# mcuCore.net
KiCad netlist of a schematic drawn in Altium Designer
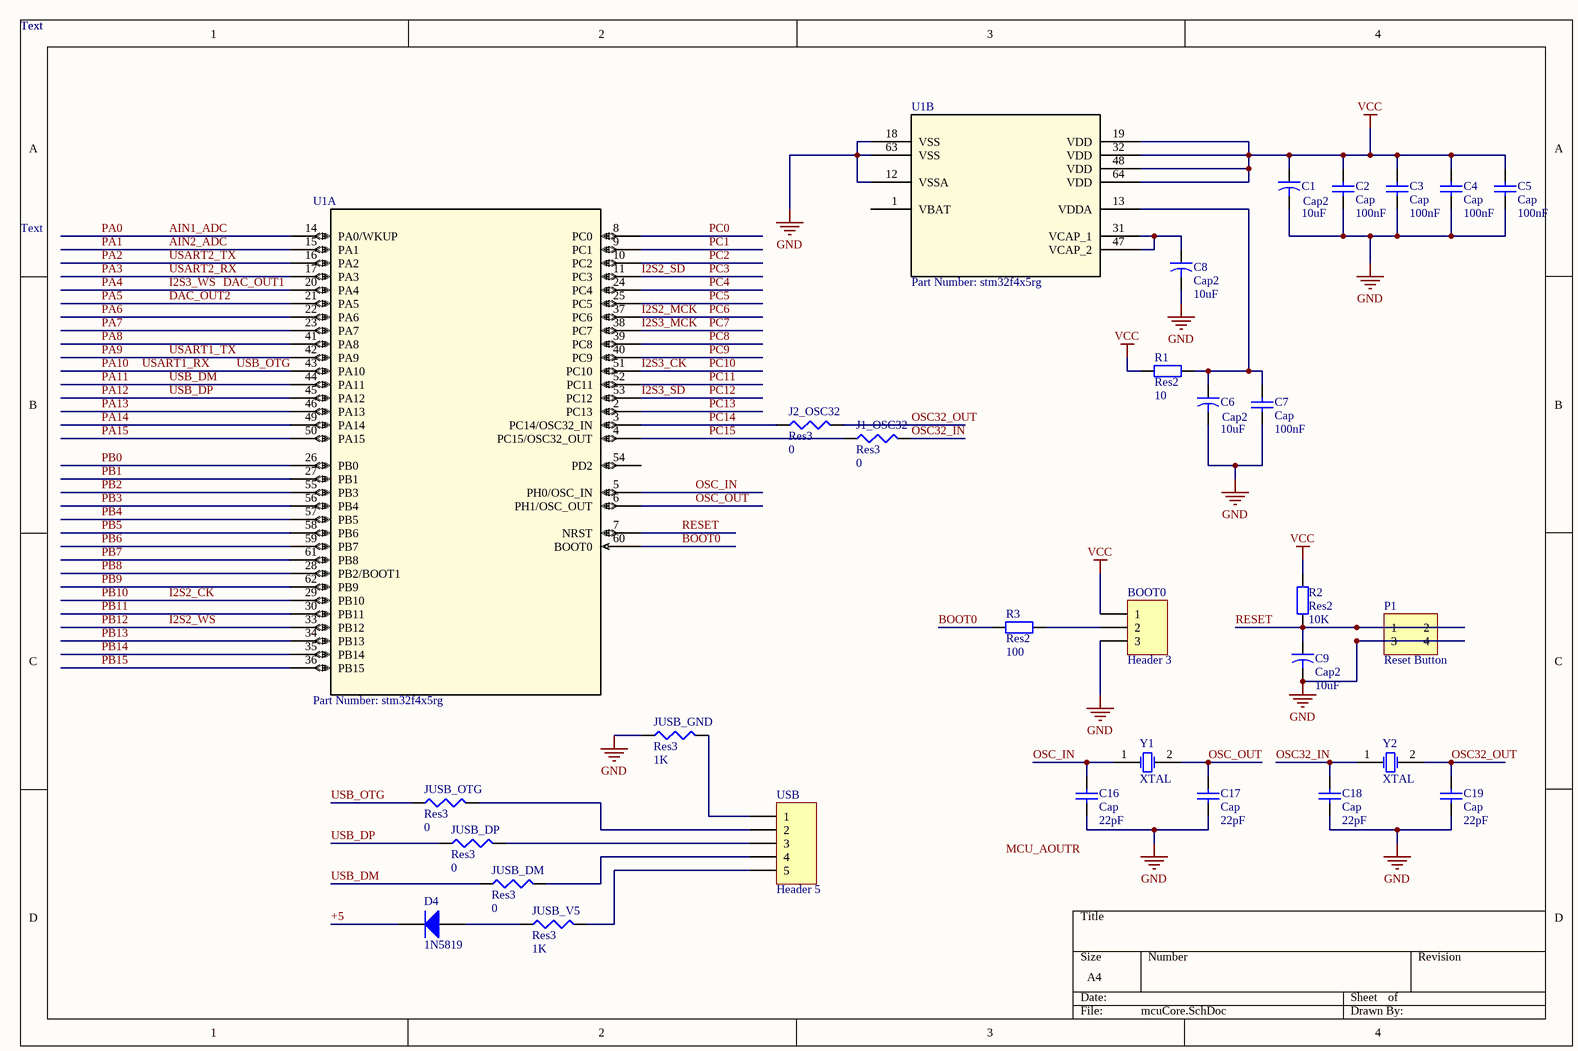
[diagram p0: mcuCore.SchDoc]

(export (version "E")
  (design (tool "Eeschema 10.0.6"))
  (components
    (comp (ref "BOOT0")
      (value "Header 3")
      (footprint "HDR1X3")
      (description "Header, 3-Pin")
      (fields (field (name "PUBLISHER") "Altium Limited"))
      (libsource (lib "Miscellaneous Connectors") (part "Header 3"))
    )
    (comp (ref "C1")
      (value "Cap2")
      (footprint "Cap5x10")
      (description "Capacitor")
      (fields (field (name "ALTIUM_VALUE") "10uF") (field (name "PUBLISHER") "Altium Limited"))
      (libsource (lib "Miscellaneous Devices") (part "Cap2"))
    )
    (comp (ref "C2")
      (value "Cap")
      (footprint "1608[0603]")
      (description "Capacitor")
      (fields (field (name "ALTIUM_VALUE") "100nF") (field (name "PUBLISHER") "Altium Limited"))
      (libsource (lib "Miscellaneous Devices") (part "Cap"))
    )
    (comp (ref "C3")
      (value "Cap")
      (footprint "1608[0603]")
      (description "Capacitor")
      (fields (field (name "ALTIUM_VALUE") "100nF") (field (name "PUBLISHER") "Altium Limited"))
      (libsource (lib "Miscellaneous Devices") (part "Cap"))
    )
    (comp (ref "C4")
      (value "Cap")
      (footprint "1608[0603]")
      (description "Capacitor")
      (fields (field (name "ALTIUM_VALUE") "100nF") (field (name "PUBLISHER") "Altium Limited"))
      (libsource (lib "Miscellaneous Devices") (part "Cap"))
    )
    (comp (ref "C5")
      (value "Cap")
      (footprint "1608[0603]")
      (description "Capacitor")
      (fields (field (name "ALTIUM_VALUE") "100nF") (field (name "PUBLISHER") "Altium Limited"))
      (libsource (lib "Miscellaneous Devices") (part "Cap"))
    )
    (comp (ref "C6")
      (value "Cap2")
      (footprint "Cap5x10")
      (description "Capacitor")
      (fields (field (name "ALTIUM_VALUE") "10uF") (field (name "PUBLISHER") "Altium Limited"))
      (libsource (lib "Miscellaneous Devices") (part "Cap2"))
    )
    (comp (ref "C7")
      (value "Cap")
      (footprint "1608[0603]")
      (description "Capacitor")
      (fields (field (name "ALTIUM_VALUE") "100nF") (field (name "PUBLISHER") "Altium Limited"))
      (libsource (lib "Miscellaneous Devices") (part "Cap"))
    )
    (comp (ref "C8")
      (value "Cap2")
      (footprint "Cap5x10")
      (description "Capacitor")
      (fields (field (name "ALTIUM_VALUE") "10uF") (field (name "PUBLISHER") "Altium Limited"))
      (libsource (lib "Miscellaneous Devices") (part "Cap2"))
    )
    (comp (ref "C9")
      (value "Cap2")
      (footprint "Cap5x10")
      (description "Capacitor")
      (fields (field (name "ALTIUM_VALUE") "10uF") (field (name "PUBLISHER") "Altium Limited"))
      (libsource (lib "Miscellaneous Devices") (part "Cap2"))
    )
    (comp (ref "C16")
      (value "Cap")
      (footprint "1608[0603]")
      (description "Capacitor")
      (fields (field (name "ALTIUM_VALUE") "22pF") (field (name "PUBLISHER") "Altium Limited"))
      (libsource (lib "Miscellaneous Devices") (part "Cap"))
    )
    (comp (ref "C17")
      (value "Cap")
      (footprint "1608[0603]")
      (description "Capacitor")
      (fields (field (name "ALTIUM_VALUE") "22pF") (field (name "PUBLISHER") "Altium Limited"))
      (libsource (lib "Miscellaneous Devices") (part "Cap"))
    )
    (comp (ref "C18")
      (value "Cap")
      (footprint "1608[0603]")
      (description "Capacitor")
      (fields (field (name "ALTIUM_VALUE") "22pF") (field (name "PUBLISHER") "Altium Limited"))
      (libsource (lib "Miscellaneous Devices") (part "Cap"))
    )
    (comp (ref "C19")
      (value "Cap")
      (footprint "1608[0603]")
      (description "Capacitor")
      (fields (field (name "ALTIUM_VALUE") "22pF") (field (name "PUBLISHER") "Altium Limited"))
      (libsource (lib "Miscellaneous Devices") (part "Cap"))
    )
    (comp (ref "D4")
      (value "1N5819")
      (footprint "425")
      (description "High Conductance Fast Diode")
      (fields (field (name "PUBLISHER") "Altium Limited"))
      (libsource (lib "Miscellaneous Devices") (part "Diode 1N4148"))
    )
    (comp (ref "J1_OSC32")
      (value "Res3")
      (footprint "JUMPER2")
      (description "Resistor")
      (fields (field (name "ALTIUM_VALUE") "0") (field (name "PUBLISHER") "Altium Limited"))
      (libsource (lib "Miscellaneous Devices") (part "Res3"))
    )
    (comp (ref "J2_OSC32")
      (value "Res3")
      (footprint "JUMPER2")
      (description "Resistor")
      (fields (field (name "ALTIUM_VALUE") "0") (field (name "PUBLISHER") "Altium Limited"))
      (libsource (lib "Miscellaneous Devices") (part "Res3"))
    )
    (comp (ref "JUSB_DM")
      (value "Res3")
      (footprint "JUMPER2")
      (description "Resistor")
      (fields (field (name "ALTIUM_VALUE") "0") (field (name "PUBLISHER") "Altium Limited"))
      (libsource (lib "Miscellaneous Devices") (part "Res3"))
    )
    (comp (ref "JUSB_DP")
      (value "Res3")
      (footprint "JUMPER2")
      (description "Resistor")
      (fields (field (name "ALTIUM_VALUE") "0") (field (name "PUBLISHER") "Altium Limited"))
      (libsource (lib "Miscellaneous Devices") (part "Res3"))
    )
    (comp (ref "JUSB_GND")
      (value "Res3")
      (footprint "JUMPER2")
      (description "Resistor")
      (fields (field (name "ALTIUM_VALUE") "1K") (field (name "PUBLISHER") "Altium Limited"))
      (libsource (lib "Miscellaneous Devices") (part "Res3"))
    )
    (comp (ref "JUSB_OTG")
      (value "Res3")
      (footprint "JUMPER2")
      (description "Resistor")
      (fields (field (name "ALTIUM_VALUE") "0") (field (name "PUBLISHER") "Altium Limited"))
      (libsource (lib "Miscellaneous Devices") (part "Res3"))
    )
    (comp (ref "JUSB_V5")
      (value "Res3")
      (footprint "JUMPER2")
      (description "Resistor")
      (fields (field (name "ALTIUM_VALUE") "1K") (field (name "PUBLISHER") "Altium Limited"))
      (libsource (lib "Miscellaneous Devices") (part "Res3"))
    )
    (comp (ref "P1")
      (value "Reset Button")
      (footprint "DC_Jack")
      (description "Header, 2-Pin, Dual row")
      (fields (field (name "PUBLISHER") "Altium Limited"))
      (libsource (lib "Miscellaneous Connectors") (part "Header 2X2"))
    )
    (comp (ref "R1")
      (value "Res2")
      (footprint "AXIAL-0.4")
      (description "Resistor")
      (fields (field (name "ALTIUM_VALUE") "10") (field (name "PUBLISHER") "Altium Limited"))
      (libsource (lib "Miscellaneous Devices") (part "Res2"))
    )
    (comp (ref "R2")
      (value "Res2")
      (footprint "J1-0603")
      (description "Resistor")
      (fields (field (name "ALTIUM_VALUE") "10K") (field (name "PUBLISHER") "Altium Limited"))
      (libsource (lib "") (part "Res2_1"))
    )
    (comp (ref "R3")
      (value "Res2")
      (footprint "J1-0603")
      (description "Resistor")
      (fields (field (name "ALTIUM_VALUE") "100") (field (name "PUBLISHER") "Altium Limited"))
      (libsource (lib "Miscellaneous Devices") (part "Res2"))
    )
    (comp (ref "U1")
      (value "Part Number: stm32f4x5rg")
      (footprint "LQFP64-10x10mm")
      (description "No Description Available")
      (fields
        (field (name "MANUFACTURER_PART_NUMBER") "stm32f4x5rg")
        (field (name "COPYRIGHT") "Copyright (C) 2016 Accelerated Designs. All rights reserved")
      )
      (libsource (lib "stm32f405rg") (part "STM32F4x5RG"))
    )
    (comp (ref "USB")
      (value "Header 5")
      (footprint "Micro_USB")
      (description "Header, 5-Pin")
      (fields (field (name "PUBLISHER") "Altium Limited"))
      (libsource (lib "Miscellaneous Connectors") (part "Header 5"))
    )
    (comp (ref "Y1")
      (value "XTAL")
      (footprint "XTAL_8M")
      (description "Crystal Oscillator")
      (fields (field (name "PUBLISHER") "Altium Limited"))
      (libsource (lib "Miscellaneous Devices") (part "XTAL"))
    )
    (comp (ref "Y2")
      (value "XTAL")
      (footprint "XTAL_32k")
      (description "Crystal Oscillator")
      (fields (field (name "PUBLISHER") "Altium Limited"))
      (libsource (lib "Miscellaneous Devices") (part "XTAL"))
    )
  )
  (nets
    (net (code "1") (name "/+5") (class "Default")
      (node (ref "D4") (pin "2") (pinfunction "K_2") (pintype "passive"))
    )
    (net (code "2") (name "/AIN1_ADC") (class "Default")
      (node (ref "U1") (pin "14") (pinfunction "PA0/WKUP_14") (pintype "bidirectional"))
    )
    (net (code "3") (name "/AIN2_ADC") (class "Default")
      (node (ref "U1") (pin "15") (pinfunction "PA1_15") (pintype "bidirectional"))
    )
    (net (code "4") (name "/BOOT0") (class "Default")
      (node (ref "R3") (pin "1") (pinfunction "1_1") (pintype "passive"))
      (node (ref "U1") (pin "60") (pinfunction "BOOT0_60") (pintype "input"))
    )
    (net (code "5") (name "/DAC_OUT1") (class "Default")
      (node (ref "U1") (pin "20") (pinfunction "PA4_20") (pintype "bidirectional"))
    )
    (net (code "6") (name "/DAC_OUT2") (class "Default")
      (node (ref "U1") (pin "21") (pinfunction "PA5_21") (pintype "bidirectional"))
    )
    (net (code "7") (name "/I2S2_CK") (class "Default")
      (node (ref "U1") (pin "29") (pinfunction "PB10_29") (pintype "bidirectional"))
    )
    (net (code "8") (name "/I2S2_MCK") (class "Default")
      (node (ref "U1") (pin "37") (pinfunction "PC6_37") (pintype "bidirectional"))
    )
    (net (code "9") (name "/I2S2_SD") (class "Default")
      (node (ref "U1") (pin "11") (pinfunction "PC3_11") (pintype "bidirectional"))
    )
    (net (code "10") (name "/I2S2_WS") (class "Default")
      (node (ref "U1") (pin "33") (pinfunction "PB12_33") (pintype "bidirectional"))
    )
    (net (code "11") (name "/I2S3_CK") (class "Default")
      (node (ref "U1") (pin "51") (pinfunction "PC10_51") (pintype "bidirectional"))
    )
    (net (code "12") (name "/I2S3_MCK") (class "Default")
      (node (ref "U1") (pin "38") (pinfunction "PC7_38") (pintype "bidirectional"))
    )
    (net (code "13") (name "/I2S3_SD") (class "Default")
      (node (ref "U1") (pin "53") (pinfunction "PC12_53") (pintype "bidirectional"))
    )
    (net (code "15") (name "/OSC32_IN") (class "Default")
      (node (ref "C18") (pin "2") (pinfunction "2_2") (pintype "passive"))
      (node (ref "J1_OSC32") (pin "2") (pinfunction "2_2") (pintype "passive"))
      (node (ref "Y2") (pin "1") (pinfunction "OSC1_1") (pintype "passive"))
    )
    (net (code "16") (name "/OSC32_OUT") (class "Default")
      (node (ref "C19") (pin "2") (pinfunction "2_2") (pintype "passive"))
      (node (ref "J2_OSC32") (pin "2") (pinfunction "2_2") (pintype "passive"))
      (node (ref "Y2") (pin "2") (pinfunction "OSC2_2") (pintype "passive"))
    )
    (net (code "17") (name "/OSC_IN") (class "Default")
      (node (ref "C16") (pin "2") (pinfunction "2_2") (pintype "passive"))
      (node (ref "U1") (pin "5") (pinfunction "PH0/OSC_IN_5") (pintype "bidirectional"))
      (node (ref "Y1") (pin "1") (pinfunction "OSC1_1") (pintype "passive"))
    )
    (net (code "18") (name "/OSC_OUT") (class "Default")
      (node (ref "C17") (pin "2") (pinfunction "2_2") (pintype "passive"))
      (node (ref "U1") (pin "6") (pinfunction "PH1/OSC_OUT_6") (pintype "bidirectional"))
      (node (ref "Y1") (pin "2") (pinfunction "OSC2_2") (pintype "passive"))
    )
    (net (code "19") (name "/PA2") (class "Default")
      (node (ref "U1") (pin "16") (pinfunction "PA2_16") (pintype "bidirectional"))
    )
    (net (code "20") (name "/PA3") (class "Default")
      (node (ref "U1") (pin "17") (pinfunction "PA3_17") (pintype "bidirectional"))
    )
    (net (code "21") (name "/PA6") (class "Default")
      (node (ref "U1") (pin "22") (pinfunction "PA6_22") (pintype "bidirectional"))
    )
    (net (code "22") (name "/PA7") (class "Default")
      (node (ref "U1") (pin "23") (pinfunction "PA7_23") (pintype "bidirectional"))
    )
    (net (code "23") (name "/PA8") (class "Default")
      (node (ref "U1") (pin "41") (pinfunction "PA8_41") (pintype "bidirectional"))
    )
    (net (code "24") (name "/PA9") (class "Default")
      (node (ref "U1") (pin "42") (pinfunction "PA9_42") (pintype "bidirectional"))
    )
    (net (code "25") (name "/PA10") (class "Default")
      (node (ref "JUSB_OTG") (pin "1") (pinfunction "1_1") (pintype "passive"))
      (node (ref "U1") (pin "43") (pinfunction "PA10_43") (pintype "bidirectional"))
    )
    (net (code "26") (name "/PA11") (class "Default")
      (node (ref "JUSB_DM") (pin "1") (pinfunction "1_1") (pintype "passive"))
      (node (ref "U1") (pin "44") (pinfunction "PA11_44") (pintype "bidirectional"))
    )
    (net (code "27") (name "/PA12") (class "Default")
      (node (ref "JUSB_DP") (pin "1") (pinfunction "1_1") (pintype "passive"))
      (node (ref "U1") (pin "45") (pinfunction "PA12_45") (pintype "bidirectional"))
    )
    (net (code "28") (name "/PA13") (class "Default")
      (node (ref "U1") (pin "46") (pinfunction "PA13_46") (pintype "bidirectional"))
    )
    (net (code "29") (name "/PA14") (class "Default")
      (node (ref "U1") (pin "49") (pinfunction "PA14_49") (pintype "bidirectional"))
    )
    (net (code "30") (name "/PA15") (class "Default")
      (node (ref "U1") (pin "50") (pinfunction "PA15_50") (pintype "bidirectional"))
    )
    (net (code "31") (name "/PB0") (class "Default")
      (node (ref "U1") (pin "26") (pinfunction "PB0_26") (pintype "bidirectional"))
    )
    (net (code "32") (name "/PB1") (class "Default")
      (node (ref "U1") (pin "27") (pinfunction "PB1_27") (pintype "bidirectional"))
    )
    (net (code "33") (name "/PB2") (class "Default")
      (node (ref "U1") (pin "55") (pinfunction "PB3_55") (pintype "bidirectional"))
    )
    (net (code "34") (name "/PB3") (class "Default")
      (node (ref "U1") (pin "56") (pinfunction "PB4_56") (pintype "bidirectional"))
    )
    (net (code "35") (name "/PB4") (class "Default")
      (node (ref "U1") (pin "57") (pinfunction "PB5_57") (pintype "bidirectional"))
    )
    (net (code "36") (name "/PB5") (class "Default")
      (node (ref "U1") (pin "58") (pinfunction "PB6_58") (pintype "bidirectional"))
    )
    (net (code "37") (name "/PB6") (class "Default")
      (node (ref "U1") (pin "59") (pinfunction "PB7_59") (pintype "bidirectional"))
    )
    (net (code "38") (name "/PB7") (class "Default")
      (node (ref "U1") (pin "61") (pinfunction "PB8_61") (pintype "bidirectional"))
    )
    (net (code "39") (name "/PB8") (class "Default")
      (node (ref "U1") (pin "28") (pinfunction "PB2/BOOT1_28") (pintype "bidirectional"))
    )
    (net (code "40") (name "/PB9") (class "Default")
      (node (ref "U1") (pin "62") (pinfunction "PB9_62") (pintype "bidirectional"))
    )
    (net (code "41") (name "/PB11") (class "Default")
      (node (ref "U1") (pin "30") (pinfunction "PB11_30") (pintype "bidirectional"))
    )
    (net (code "42") (name "/PB13") (class "Default")
      (node (ref "U1") (pin "34") (pinfunction "PB13_34") (pintype "bidirectional"))
    )
    (net (code "43") (name "/PB14") (class "Default")
      (node (ref "U1") (pin "35") (pinfunction "PB14_35") (pintype "bidirectional"))
    )
    (net (code "44") (name "/PB15") (class "Default")
      (node (ref "U1") (pin "36") (pinfunction "PB15_36") (pintype "bidirectional"))
    )
    (net (code "45") (name "/PC0") (class "Default")
      (node (ref "U1") (pin "8") (pinfunction "PC0_8") (pintype "bidirectional"))
    )
    (net (code "46") (name "/PC1") (class "Default")
      (node (ref "U1") (pin "9") (pinfunction "PC1_9") (pintype "bidirectional"))
    )
    (net (code "47") (name "/PC2") (class "Default")
      (node (ref "U1") (pin "10") (pinfunction "PC2_10") (pintype "bidirectional"))
    )
    (net (code "48") (name "/PC4") (class "Default")
      (node (ref "U1") (pin "24") (pinfunction "PC4_24") (pintype "bidirectional"))
    )
    (net (code "49") (name "/PC5") (class "Default")
      (node (ref "U1") (pin "25") (pinfunction "PC5_25") (pintype "bidirectional"))
    )
    (net (code "50") (name "/PC8") (class "Default")
      (node (ref "U1") (pin "39") (pinfunction "PC8_39") (pintype "bidirectional"))
    )
    (net (code "51") (name "/PC9") (class "Default")
      (node (ref "U1") (pin "40") (pinfunction "PC9_40") (pintype "bidirectional"))
    )
    (net (code "52") (name "/PC11") (class "Default")
      (node (ref "U1") (pin "52") (pinfunction "PC11_52") (pintype "bidirectional"))
    )
    (net (code "53") (name "/PC13") (class "Default")
      (node (ref "U1") (pin "2") (pinfunction "PC13_2") (pintype "bidirectional"))
    )
    (net (code "54") (name "/PC14") (class "Default")
      (node (ref "J2_OSC32") (pin "1") (pinfunction "1_1") (pintype "passive"))
      (node (ref "U1") (pin "3") (pinfunction "PC14/OSC32_IN_3") (pintype "bidirectional"))
    )
    (net (code "55") (name "/PC15") (class "Default")
      (node (ref "J1_OSC32") (pin "1") (pinfunction "1_1") (pintype "passive"))
      (node (ref "U1") (pin "4") (pinfunction "PC15/OSC32_OUT_4") (pintype "bidirectional"))
    )
    (net (code "56") (name "/RESET") (class "Default")
      (node (ref "C9") (pin "1") (pinfunction "1_1") (pintype "passive"))
      (node (ref "P1") (pin "1") (pinfunction "1_1") (pintype "passive"))
      (node (ref "P1") (pin "2") (pinfunction "2_2") (pintype "passive"))
      (node (ref "R2") (pin "1") (pinfunction "1_1") (pintype "passive"))
      (node (ref "U1") (pin "7") (pinfunction "NRST_7") (pintype "bidirectional"))
    )
    (net (code "57") (name "GND") (class "Default")
      (node (ref "BOOT0") (pin "3") (pinfunction "3_3") (pintype "passive"))
      (node (ref "C1") (pin "2") (pinfunction "2_2") (pintype "passive"))
      (node (ref "C16") (pin "1") (pinfunction "1_1") (pintype "passive"))
      (node (ref "C17") (pin "1") (pinfunction "1_1") (pintype "passive"))
      (node (ref "C18") (pin "1") (pinfunction "1_1") (pintype "passive"))
      (node (ref "C19") (pin "1") (pinfunction "1_1") (pintype "passive"))
      (node (ref "C2") (pin "1") (pinfunction "1_1") (pintype "passive"))
      (node (ref "C3") (pin "1") (pinfunction "1_1") (pintype "passive"))
      (node (ref "C4") (pin "1") (pinfunction "1_1") (pintype "passive"))
      (node (ref "C5") (pin "1") (pinfunction "1_1") (pintype "passive"))
      (node (ref "C6") (pin "2") (pinfunction "2_2") (pintype "passive"))
      (node (ref "C7") (pin "1") (pinfunction "1_1") (pintype "passive"))
      (node (ref "C8") (pin "2") (pinfunction "2_2") (pintype "passive"))
      (node (ref "C9") (pin "2") (pinfunction "2_2") (pintype "passive"))
      (node (ref "JUSB_GND") (pin "1") (pinfunction "1_1") (pintype "passive"))
      (node (ref "P1") (pin "3") (pinfunction "3_3") (pintype "passive"))
      (node (ref "P1") (pin "4") (pinfunction "4_4") (pintype "passive"))
      (node (ref "U1") (pin "12") (pinfunction "VSSA_12") (pintype "power_in"))
      (node (ref "U1") (pin "18") (pinfunction "VSS_18") (pintype "power_in"))
      (node (ref "U1") (pin "63") (pinfunction "VSS_63") (pintype "power_in"))
    )
    (net (code "58") (name "Net-(BOOT0-Pad2)") (class "Default")
      (node (ref "BOOT0") (pin "2") (pinfunction "2_2") (pintype "passive"))
      (node (ref "R3") (pin "2") (pinfunction "2_2") (pintype "passive"))
    )
    (net (code "59") (name "Net-(D4-A)") (class "Default")
      (node (ref "D4") (pin "1") (pinfunction "A_1") (pintype "passive"))
      (node (ref "JUSB_V5") (pin "1") (pinfunction "1_1") (pintype "passive"))
    )
    (net (code "60") (name "Net-(JUSB_DM-Pad2)") (class "Default")
      (node (ref "JUSB_DM") (pin "2") (pinfunction "2_2") (pintype "passive"))
      (node (ref "USB") (pin "4") (pinfunction "4_4") (pintype "passive"))
    )
    (net (code "61") (name "Net-(JUSB_DP-Pad2)") (class "Default")
      (node (ref "JUSB_DP") (pin "2") (pinfunction "2_2") (pintype "passive"))
      (node (ref "USB") (pin "3") (pinfunction "3_3") (pintype "passive"))
    )
    (net (code "62") (name "Net-(JUSB_GND-Pad2)") (class "Default")
      (node (ref "JUSB_GND") (pin "2") (pinfunction "2_2") (pintype "passive"))
      (node (ref "USB") (pin "1") (pinfunction "1_1") (pintype "passive"))
    )
    (net (code "63") (name "Net-(JUSB_OTG-Pad2)") (class "Default")
      (node (ref "JUSB_OTG") (pin "2") (pinfunction "2_2") (pintype "passive"))
      (node (ref "USB") (pin "2") (pinfunction "2_2") (pintype "passive"))
    )
    (net (code "64") (name "Net-(JUSB_V5-Pad2)") (class "Default")
      (node (ref "JUSB_V5") (pin "2") (pinfunction "2_2") (pintype "passive"))
      (node (ref "USB") (pin "5") (pinfunction "5_5") (pintype "passive"))
    )
    (net (code "65") (name "Net-(U1B-VCAP_1)") (class "Default")
      (node (ref "C8") (pin "1") (pinfunction "1_1") (pintype "passive"))
      (node (ref "U1") (pin "31") (pinfunction "VCAP_1_31") (pintype "power_in"))
      (node (ref "U1") (pin "47") (pinfunction "VCAP_2_47") (pintype "power_in"))
    )
    (net (code "66") (name "Net-(U1B-VDDA)") (class "Default")
      (node (ref "C6") (pin "1") (pinfunction "1_1") (pintype "passive"))
      (node (ref "C7") (pin "2") (pinfunction "2_2") (pintype "passive"))
      (node (ref "R1") (pin "2") (pinfunction "2_2") (pintype "passive"))
      (node (ref "U1") (pin "13") (pinfunction "VDDA_13") (pintype "power_in"))
    )
    (net (code "67") (name "VCC") (class "Default")
      (node (ref "BOOT0") (pin "1") (pinfunction "1_1") (pintype "passive"))
      (node (ref "C1") (pin "1") (pinfunction "1_1") (pintype "passive"))
      (node (ref "C2") (pin "2") (pinfunction "2_2") (pintype "passive"))
      (node (ref "C3") (pin "2") (pinfunction "2_2") (pintype "passive"))
      (node (ref "C4") (pin "2") (pinfunction "2_2") (pintype "passive"))
      (node (ref "C5") (pin "2") (pinfunction "2_2") (pintype "passive"))
      (node (ref "R1") (pin "1") (pinfunction "1_1") (pintype "passive"))
      (node (ref "R2") (pin "2") (pinfunction "2_2") (pintype "passive"))
      (node (ref "U1") (pin "19") (pinfunction "VDD_19") (pintype "power_in"))
      (node (ref "U1") (pin "32") (pinfunction "VDD_32") (pintype "power_in"))
      (node (ref "U1") (pin "48") (pinfunction "VDD_48") (pintype "power_in"))
      (node (ref "U1") (pin "64") (pinfunction "VDD_64") (pintype "power_in"))
    )
    (net (code "68") (name "unconnected-(U1A-PD2-Pad54)") (class "Default")
      (node (ref "U1") (pin "54") (pinfunction "PD2_54") (pintype "bidirectional"))
    )
    (net (code "69") (name "unconnected-(U1B-VBAT-Pad1)") (class "Default")
      (node (ref "U1") (pin "1") (pinfunction "VBAT_1") (pintype "power_in"))
    )
  )
)
